# Expan.net
KiCad netlist of a schematic drawn in Altium Designer
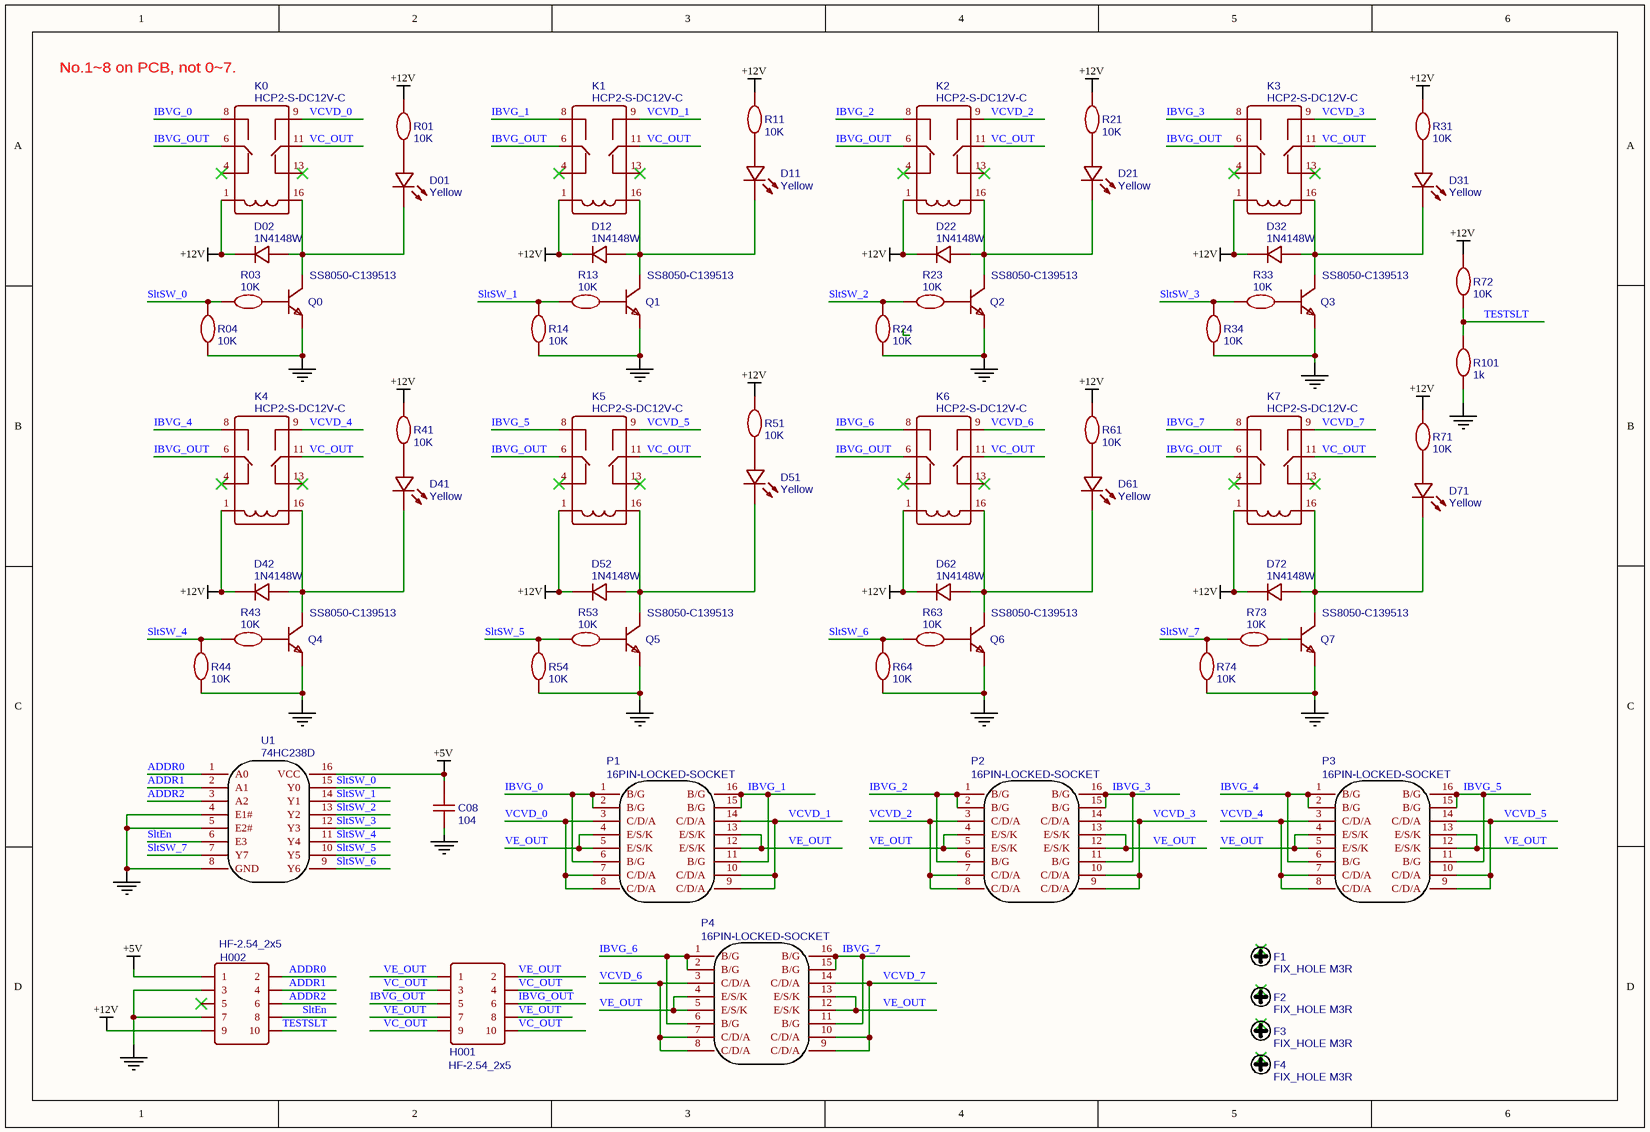
[diagram p0: Expan.schdoc]

(export (version "E")
  (design (tool "Eeschema 10.0.6"))
  (components
    (comp (ref "C08")
      (value "104")
      (footprint "C0805")
      (libsource (lib "altium-import") (part "root_0_104_"))
    )
    (comp (ref "D01")
      (value "Yellow")
      (footprint "LED-TH_BD4.0-P2.54-FD")
      (fields
        (field (name "BOM_SUPPLIER PART") "C396687")
        (field (name "BOM_MANUFACTURER PART") "DY-204URD/SN-A3(EL)")
        (field (name "CONTRIBUTOR") "LCSC")
      )
      (libsource (lib "altium-import") (part "root_3_Yellow_"))
    )
    (comp (ref "D02")
      (value "1N4148W")
      (footprint "SOD-123_L2.8-W1.8-LS3.7-FD")
      (fields (field (name "BOM_SUPPLIER PART") "C81598"))
      (libsource (lib "altium-import") (part "root_2_1N4148W_"))
    )
    (comp (ref "D11")
      (value "Yellow")
      (footprint "LED-TH_BD4.0-P2.54-FD")
      (fields
        (field (name "BOM_SUPPLIER PART") "C396687")
        (field (name "BOM_MANUFACTURER PART") "DY-204URD/SN-A3(EL)")
        (field (name "CONTRIBUTOR") "LCSC")
      )
      (libsource (lib "altium-import") (part "root_3_Yellow_"))
    )
    (comp (ref "D12")
      (value "1N4148W")
      (footprint "SOD-123_L2.8-W1.8-LS3.7-FD")
      (fields (field (name "BOM_SUPPLIER PART") "C81598"))
      (libsource (lib "altium-import") (part "root_2_1N4148W_"))
    )
    (comp (ref "D21")
      (value "Yellow")
      (footprint "LED-TH_BD4.0-P2.54-FD")
      (fields
        (field (name "BOM_SUPPLIER PART") "C396687")
        (field (name "BOM_MANUFACTURER PART") "DY-204URD/SN-A3(EL)")
        (field (name "CONTRIBUTOR") "LCSC")
      )
      (libsource (lib "altium-import") (part "root_3_Yellow_"))
    )
    (comp (ref "D22")
      (value "1N4148W")
      (footprint "SOD-123_L2.8-W1.8-LS3.7-FD")
      (fields (field (name "BOM_SUPPLIER PART") "C81598"))
      (libsource (lib "altium-import") (part "root_2_1N4148W_"))
    )
    (comp (ref "D31")
      (value "Yellow")
      (footprint "LED-TH_BD4.0-P2.54-FD")
      (fields
        (field (name "BOM_SUPPLIER PART") "C396687")
        (field (name "BOM_MANUFACTURER PART") "DY-204URD/SN-A3(EL)")
        (field (name "CONTRIBUTOR") "LCSC")
      )
      (libsource (lib "altium-import") (part "root_3_Yellow_"))
    )
    (comp (ref "D32")
      (value "1N4148W")
      (footprint "SOD-123_L2.8-W1.8-LS3.7-FD")
      (fields (field (name "BOM_SUPPLIER PART") "C81598"))
      (libsource (lib "altium-import") (part "root_2_1N4148W_"))
    )
    (comp (ref "D41")
      (value "Yellow")
      (footprint "LED-TH_BD4.0-P2.54-FD")
      (fields
        (field (name "BOM_SUPPLIER PART") "C396687")
        (field (name "BOM_MANUFACTURER PART") "DY-204URD/SN-A3(EL)")
        (field (name "CONTRIBUTOR") "LCSC")
      )
      (libsource (lib "altium-import") (part "root_3_Yellow_"))
    )
    (comp (ref "D42")
      (value "1N4148W")
      (footprint "SOD-123_L2.8-W1.8-LS3.7-FD")
      (fields (field (name "BOM_SUPPLIER PART") "C81598"))
      (libsource (lib "altium-import") (part "root_2_1N4148W_"))
    )
    (comp (ref "D51")
      (value "Yellow")
      (footprint "LED-TH_BD4.0-P2.54-FD")
      (fields
        (field (name "BOM_SUPPLIER PART") "C396687")
        (field (name "BOM_MANUFACTURER PART") "DY-204URD/SN-A3(EL)")
        (field (name "CONTRIBUTOR") "LCSC")
      )
      (libsource (lib "altium-import") (part "root_3_Yellow_"))
    )
    (comp (ref "D52")
      (value "1N4148W")
      (footprint "SOD-123_L2.8-W1.8-LS3.7-FD")
      (fields (field (name "BOM_SUPPLIER PART") "C81598"))
      (libsource (lib "altium-import") (part "root_2_1N4148W_"))
    )
    (comp (ref "D61")
      (value "Yellow")
      (footprint "LED-TH_BD4.0-P2.54-FD")
      (fields
        (field (name "BOM_SUPPLIER PART") "C396687")
        (field (name "BOM_MANUFACTURER PART") "DY-204URD/SN-A3(EL)")
        (field (name "CONTRIBUTOR") "LCSC")
      )
      (libsource (lib "altium-import") (part "root_3_Yellow_"))
    )
    (comp (ref "D62")
      (value "1N4148W")
      (footprint "SOD-123_L2.8-W1.8-LS3.7-FD")
      (fields (field (name "BOM_SUPPLIER PART") "C81598"))
      (libsource (lib "altium-import") (part "root_2_1N4148W_"))
    )
    (comp (ref "D71")
      (value "Yellow")
      (footprint "LED-TH_BD4.0-P2.54-FD")
      (fields
        (field (name "BOM_SUPPLIER PART") "C396687")
        (field (name "BOM_MANUFACTURER PART") "DY-204URD/SN-A3(EL)")
        (field (name "CONTRIBUTOR") "LCSC")
      )
      (libsource (lib "altium-import") (part "root_3_Yellow_"))
    )
    (comp (ref "D72")
      (value "1N4148W")
      (footprint "SOD-123_L2.8-W1.8-LS3.7-FD")
      (fields (field (name "BOM_SUPPLIER PART") "C81598"))
      (libsource (lib "altium-import") (part "root_2_1N4148W_"))
    )
    (comp (ref "F1")
      (value "FIX_HOLE M3R")
      (footprint "FIXHOLE_M3R")
      (fields (field (name "CONTRIBUTOR") "JM共享库"))
      (libsource (lib "altium-import") (part "root_0_FIX_HOLE M3R_"))
    )
    (comp (ref "F2")
      (value "FIX_HOLE M3R")
      (footprint "FIXHOLE_M3R")
      (fields (field (name "CONTRIBUTOR") "JM共享库"))
      (libsource (lib "altium-import") (part "root_0_FIX_HOLE M3R_"))
    )
    (comp (ref "F3")
      (value "FIX_HOLE M3R")
      (footprint "FIXHOLE_M3R")
      (fields (field (name "CONTRIBUTOR") "JM共享库"))
      (libsource (lib "altium-import") (part "root_0_FIX_HOLE M3R_"))
    )
    (comp (ref "F4")
      (value "FIX_HOLE M3R")
      (footprint "FIXHOLE_M3R")
      (fields (field (name "CONTRIBUTOR") "JM共享库"))
      (libsource (lib "altium-import") (part "root_0_FIX_HOLE M3R_"))
    )
    (comp (ref "H001")
      (value "HF-2.54_2x5")
      (footprint "HDR-TH_10P-P2.54-V-R2-C5-S2.54")
      (fields
        (field (name "BOM_MANUFACTURER PART") "220S-2*5P H=8.5MM Ytype Gold-plated")
        (field (name "BOM_SUPPLIER PART") "C124423")
      )
      (libsource (lib "altium-import") (part "root_0_HF-2.54_2x5_"))
    )
    (comp (ref "H002")
      (value "HF-2.54_2x5")
      (footprint "HDR-TH_10P-P2.54-V-R2-C5-S2.54")
      (fields
        (field (name "BOM_MANUFACTURER PART") "220S-2*5P H=8.5MM Ytype Gold-plated")
        (field (name "BOM_SUPPLIER PART") "C124423")
      )
      (libsource (lib "altium-import") (part "root_0_HF-2.54_2x5_"))
    )
    (comp (ref "K0")
      (value "HCP2-S-DC12V-C")
      (footprint "RELAY-HCP2-S-C")
      (fields (field (name "BOM_SUPPLIER PART") "C125698") (field (name "CONTRIBUTOR") "LCSC"))
      (libsource (lib "altium-import") (part "root_1_HCP2-S-DC12V-C_"))
    )
    (comp (ref "K1")
      (value "HCP2-S-DC12V-C")
      (footprint "RELAY-HCP2-S-C")
      (fields (field (name "BOM_SUPPLIER PART") "C125698") (field (name "CONTRIBUTOR") "LCSC"))
      (libsource (lib "altium-import") (part "root_1_HCP2-S-DC12V-C_"))
    )
    (comp (ref "K2")
      (value "HCP2-S-DC12V-C")
      (footprint "RELAY-HCP2-S-C")
      (fields (field (name "BOM_SUPPLIER PART") "C125698") (field (name "CONTRIBUTOR") "LCSC"))
      (libsource (lib "altium-import") (part "root_1_HCP2-S-DC12V-C_"))
    )
    (comp (ref "K3")
      (value "HCP2-S-DC12V-C")
      (footprint "RELAY-HCP2-S-C")
      (fields (field (name "BOM_SUPPLIER PART") "C125698") (field (name "CONTRIBUTOR") "LCSC"))
      (libsource (lib "altium-import") (part "root_1_HCP2-S-DC12V-C_"))
    )
    (comp (ref "K4")
      (value "HCP2-S-DC12V-C")
      (footprint "RELAY-HCP2-S-C")
      (fields (field (name "BOM_SUPPLIER PART") "C125698") (field (name "CONTRIBUTOR") "LCSC"))
      (libsource (lib "altium-import") (part "root_1_HCP2-S-DC12V-C_"))
    )
    (comp (ref "K5")
      (value "HCP2-S-DC12V-C")
      (footprint "RELAY-HCP2-S-C")
      (fields (field (name "BOM_SUPPLIER PART") "C125698") (field (name "CONTRIBUTOR") "LCSC"))
      (libsource (lib "altium-import") (part "root_1_HCP2-S-DC12V-C_"))
    )
    (comp (ref "K6")
      (value "HCP2-S-DC12V-C")
      (footprint "RELAY-HCP2-S-C")
      (fields (field (name "BOM_SUPPLIER PART") "C125698") (field (name "CONTRIBUTOR") "LCSC"))
      (libsource (lib "altium-import") (part "root_1_HCP2-S-DC12V-C_"))
    )
    (comp (ref "K7")
      (value "HCP2-S-DC12V-C")
      (footprint "RELAY-HCP2-S-C")
      (fields (field (name "BOM_SUPPLIER PART") "C125698") (field (name "CONTRIBUTOR") "LCSC"))
      (libsource (lib "altium-import") (part "root_1_HCP2-S-DC12V-C_"))
    )
    (comp (ref "P1")
      (value "16PIN-LOCKED-SOCKET")
      (footprint "16PIN-LOCKED-SOCKET")
      (fields (field (name "CONTRIBUTOR") "XTX_AE"))
      (libsource (lib "altium-import") (part "root_0_16PIN-LOCKED-SOCKET_"))
    )
    (comp (ref "P2")
      (value "16PIN-LOCKED-SOCKET")
      (footprint "16PIN-LOCKED-SOCKET")
      (fields (field (name "CONTRIBUTOR") "XTX_AE"))
      (libsource (lib "altium-import") (part "root_0_16PIN-LOCKED-SOCKET_"))
    )
    (comp (ref "P3")
      (value "16PIN-LOCKED-SOCKET")
      (footprint "16PIN-LOCKED-SOCKET")
      (fields (field (name "CONTRIBUTOR") "XTX_AE"))
      (libsource (lib "altium-import") (part "root_0_16PIN-LOCKED-SOCKET_"))
    )
    (comp (ref "P4")
      (value "16PIN-LOCKED-SOCKET")
      (footprint "16PIN-LOCKED-SOCKET")
      (fields (field (name "CONTRIBUTOR") "XTX_AE"))
      (libsource (lib "altium-import") (part "root_0_16PIN-LOCKED-SOCKET_"))
    )
    (comp (ref "Q0")
      (value "SS8050-C139513")
      (footprint "SOT-23-3_L2.9-W1.3-P1.90-LS2.4-BR")
      (fields
        (field (name "BOM_SUPPLIER PART") "C402304")
        (field (name "BOM_MANUFACTURER PART") "SS8050")
        (field (name "CONTRIBUTOR") "LCSC")
      )
      (libsource (lib "altium-import") (part "root_0_SS8050-C139513_"))
    )
    (comp (ref "Q1")
      (value "SS8050-C139513")
      (footprint "SOT-23-3_L2.9-W1.3-P1.90-LS2.4-BR")
      (fields
        (field (name "BOM_SUPPLIER PART") "C402304")
        (field (name "BOM_MANUFACTURER PART") "SS8050")
        (field (name "CONTRIBUTOR") "LCSC")
      )
      (libsource (lib "altium-import") (part "root_0_SS8050-C139513_"))
    )
    (comp (ref "Q2")
      (value "SS8050-C139513")
      (footprint "SOT-23-3_L2.9-W1.3-P1.90-LS2.4-BR")
      (fields
        (field (name "BOM_SUPPLIER PART") "C402304")
        (field (name "BOM_MANUFACTURER PART") "SS8050")
        (field (name "CONTRIBUTOR") "LCSC")
      )
      (libsource (lib "altium-import") (part "root_0_SS8050-C139513_"))
    )
    (comp (ref "Q3")
      (value "SS8050-C139513")
      (footprint "SOT-23-3_L2.9-W1.3-P1.90-LS2.4-BR")
      (fields
        (field (name "BOM_SUPPLIER PART") "C402304")
        (field (name "BOM_MANUFACTURER PART") "SS8050")
        (field (name "CONTRIBUTOR") "LCSC")
      )
      (libsource (lib "altium-import") (part "root_0_SS8050-C139513_"))
    )
    (comp (ref "Q4")
      (value "SS8050-C139513")
      (footprint "SOT-23-3_L2.9-W1.3-P1.90-LS2.4-BR")
      (fields
        (field (name "BOM_SUPPLIER PART") "C402304")
        (field (name "BOM_MANUFACTURER PART") "SS8050")
        (field (name "CONTRIBUTOR") "LCSC")
      )
      (libsource (lib "altium-import") (part "root_0_SS8050-C139513_"))
    )
    (comp (ref "Q5")
      (value "SS8050-C139513")
      (footprint "SOT-23-3_L2.9-W1.3-P1.90-LS2.4-BR")
      (fields
        (field (name "BOM_SUPPLIER PART") "C402304")
        (field (name "BOM_MANUFACTURER PART") "SS8050")
        (field (name "CONTRIBUTOR") "LCSC")
      )
      (libsource (lib "altium-import") (part "root_0_SS8050-C139513_"))
    )
    (comp (ref "Q6")
      (value "SS8050-C139513")
      (footprint "SOT-23-3_L2.9-W1.3-P1.90-LS2.4-BR")
      (fields
        (field (name "BOM_SUPPLIER PART") "C402304")
        (field (name "BOM_MANUFACTURER PART") "SS8050")
        (field (name "CONTRIBUTOR") "LCSC")
      )
      (libsource (lib "altium-import") (part "root_0_SS8050-C139513_"))
    )
    (comp (ref "Q7")
      (value "SS8050-C139513")
      (footprint "SOT-23-3_L2.9-W1.3-P1.90-LS2.4-BR")
      (fields
        (field (name "BOM_SUPPLIER PART") "C402304")
        (field (name "BOM_MANUFACTURER PART") "SS8050")
        (field (name "CONTRIBUTOR") "LCSC")
      )
      (libsource (lib "altium-import") (part "root_0_SS8050-C139513_"))
    )
    (comp (ref "R01")
      (value "10K")
      (footprint "R0805")
      (libsource (lib "altium-import") (part "root_3_10K_"))
    )
    (comp (ref "R03")
      (value "10K")
      (footprint "R0805")
      (libsource (lib "altium-import") (part "root_2_10K_"))
    )
    (comp (ref "R04")
      (value "10K")
      (footprint "R0805")
      (libsource (lib "altium-import") (part "root_3_10K_"))
    )
    (comp (ref "R11")
      (value "10K")
      (footprint "R0805")
      (libsource (lib "altium-import") (part "root_3_10K_"))
    )
    (comp (ref "R13")
      (value "10K")
      (footprint "R0805")
      (libsource (lib "altium-import") (part "root_2_10K_"))
    )
    (comp (ref "R14")
      (value "10K")
      (footprint "R0805")
      (libsource (lib "altium-import") (part "root_3_10K_"))
    )
    (comp (ref "R21")
      (value "10K")
      (footprint "R0805")
      (libsource (lib "altium-import") (part "root_3_10K_"))
    )
    (comp (ref "R23")
      (value "10K")
      (footprint "R0805")
      (libsource (lib "altium-import") (part "root_2_10K_"))
    )
    (comp (ref "R24")
      (value "10K")
      (footprint "R0805")
      (libsource (lib "altium-import") (part "root_3_10K_"))
    )
    (comp (ref "R31")
      (value "10K")
      (footprint "R0805")
      (libsource (lib "altium-import") (part "root_3_10K_"))
    )
    (comp (ref "R33")
      (value "10K")
      (footprint "R0805")
      (libsource (lib "altium-import") (part "root_2_10K_"))
    )
    (comp (ref "R34")
      (value "10K")
      (footprint "R0805")
      (libsource (lib "altium-import") (part "root_3_10K_"))
    )
    (comp (ref "R41")
      (value "10K")
      (footprint "R0805")
      (libsource (lib "altium-import") (part "root_3_10K_"))
    )
    (comp (ref "R43")
      (value "10K")
      (footprint "R0805")
      (libsource (lib "altium-import") (part "root_2_10K_"))
    )
    (comp (ref "R44")
      (value "10K")
      (footprint "R0805")
      (libsource (lib "altium-import") (part "root_3_10K_"))
    )
    (comp (ref "R51")
      (value "10K")
      (footprint "R0805")
      (libsource (lib "altium-import") (part "root_3_10K_"))
    )
    (comp (ref "R53")
      (value "10K")
      (footprint "R0805")
      (libsource (lib "altium-import") (part "root_2_10K_"))
    )
    (comp (ref "R54")
      (value "10K")
      (footprint "R0805")
      (libsource (lib "altium-import") (part "root_3_10K_"))
    )
    (comp (ref "R61")
      (value "10K")
      (footprint "R0805")
      (libsource (lib "altium-import") (part "root_3_10K_"))
    )
    (comp (ref "R63")
      (value "10K")
      (footprint "R0805")
      (libsource (lib "altium-import") (part "root_2_10K_"))
    )
    (comp (ref "R64")
      (value "10K")
      (footprint "R0805")
      (libsource (lib "altium-import") (part "root_3_10K_"))
    )
    (comp (ref "R71")
      (value "10K")
      (footprint "R0805")
      (libsource (lib "altium-import") (part "root_3_10K_"))
    )
    (comp (ref "R72")
      (value "10K")
      (footprint "R0805")
      (libsource (lib "altium-import") (part "root_3_10K_"))
    )
    (comp (ref "R73")
      (value "10K")
      (footprint "R0805")
      (libsource (lib "altium-import") (part "root_2_10K_"))
    )
    (comp (ref "R74")
      (value "10K")
      (footprint "R0805")
      (libsource (lib "altium-import") (part "root_3_10K_"))
    )
    (comp (ref "R101") (value "1k") (footprint "R0805") (libsource (lib "altium-import") (part "root_3_1k_")))
    (comp (ref "U1")
      (value "74HC238D")
      (footprint "SOIC-16_L9.9-W3.9-P1.27-LS6.0-BL")
      (fields (field (name "BOM_SUPPLIER PART") "C5620"))
      (libsource (lib "altium-import") (part "root_0_74HC238D_"))
    )
  )
  (nets
    (net (code "1") (name "+5V") (class "Default")
      (node (ref "C08") (pin "2") (pinfunction "2_2") (pintype "passive"))
      (node (ref "H002") (pin "1") (pinfunction "1_1") (pintype "passive"))
      (node (ref "U1") (pin "16") (pinfunction "VCC_16") (pintype "passive"))
    )
    (net (code "2") (name "+12V") (class "Default")
      (node (ref "D02") (pin "2") (pinfunction "K_2") (pintype "passive"))
      (node (ref "D12") (pin "2") (pinfunction "K_2") (pintype "passive"))
      (node (ref "D22") (pin "2") (pinfunction "K_2") (pintype "passive"))
      (node (ref "D32") (pin "2") (pinfunction "K_2") (pintype "passive"))
      (node (ref "D42") (pin "2") (pinfunction "K_2") (pintype "passive"))
      (node (ref "D52") (pin "2") (pinfunction "K_2") (pintype "passive"))
      (node (ref "D62") (pin "2") (pinfunction "K_2") (pintype "passive"))
      (node (ref "D72") (pin "2") (pinfunction "K_2") (pintype "passive"))
      (node (ref "H002") (pin "9") (pinfunction "9_9") (pintype "passive"))
      (node (ref "K0") (pin "1") (pinfunction "1_1") (pintype "passive"))
      (node (ref "K1") (pin "1") (pinfunction "1_1") (pintype "passive"))
      (node (ref "K2") (pin "1") (pinfunction "1_1") (pintype "passive"))
      (node (ref "K3") (pin "1") (pinfunction "1_1") (pintype "passive"))
      (node (ref "K4") (pin "1") (pinfunction "1_1") (pintype "passive"))
      (node (ref "K5") (pin "1") (pinfunction "1_1") (pintype "passive"))
      (node (ref "K6") (pin "1") (pinfunction "1_1") (pintype "passive"))
      (node (ref "K7") (pin "1") (pinfunction "1_1") (pintype "passive"))
      (node (ref "R01") (pin "1") (pinfunction "1_1") (pintype "passive"))
      (node (ref "R11") (pin "1") (pinfunction "1_1") (pintype "passive"))
      (node (ref "R21") (pin "1") (pinfunction "1_1") (pintype "passive"))
      (node (ref "R31") (pin "1") (pinfunction "1_1") (pintype "passive"))
      (node (ref "R41") (pin "1") (pinfunction "1_1") (pintype "passive"))
      (node (ref "R51") (pin "1") (pinfunction "1_1") (pintype "passive"))
      (node (ref "R61") (pin "1") (pinfunction "1_1") (pintype "passive"))
      (node (ref "R71") (pin "1") (pinfunction "1_1") (pintype "passive"))
      (node (ref "R72") (pin "1") (pinfunction "1_1") (pintype "passive"))
    )
    (net (code "3") (name "/ADDR0") (class "Default")
      (node (ref "H002") (pin "2") (pinfunction "2_2") (pintype "passive"))
      (node (ref "U1") (pin "1") (pinfunction "A0_1") (pintype "passive"))
    )
    (net (code "4") (name "/ADDR1") (class "Default")
      (node (ref "H002") (pin "4") (pinfunction "4_4") (pintype "passive"))
      (node (ref "U1") (pin "2") (pinfunction "A1_2") (pintype "passive"))
    )
    (net (code "5") (name "/ADDR2") (class "Default")
      (node (ref "H002") (pin "6") (pinfunction "6_6") (pintype "passive"))
      (node (ref "U1") (pin "3") (pinfunction "A2_3") (pintype "passive"))
    )
    (net (code "6") (name "/IBVG_0") (class "Default")
      (node (ref "K0") (pin "8") (pinfunction "8_8") (pintype "passive"))
      (node (ref "P1") (pin "1") (pinfunction "B/G_1") (pintype "passive"))
      (node (ref "P1") (pin "2") (pinfunction "B/G_2") (pintype "passive"))
      (node (ref "P1") (pin "6") (pinfunction "B/G_6") (pintype "passive"))
    )
    (net (code "7") (name "/IBVG_1") (class "Default")
      (node (ref "K1") (pin "8") (pinfunction "8_8") (pintype "passive"))
      (node (ref "P1") (pin "11") (pinfunction "B/G_11") (pintype "passive"))
      (node (ref "P1") (pin "15") (pinfunction "B/G_15") (pintype "passive"))
      (node (ref "P1") (pin "16") (pinfunction "B/G_16") (pintype "passive"))
    )
    (net (code "8") (name "/IBVG_2") (class "Default")
      (node (ref "K2") (pin "8") (pinfunction "8_8") (pintype "passive"))
      (node (ref "P2") (pin "1") (pinfunction "B/G_1") (pintype "passive"))
      (node (ref "P2") (pin "2") (pinfunction "B/G_2") (pintype "passive"))
      (node (ref "P2") (pin "6") (pinfunction "B/G_6") (pintype "passive"))
    )
    (net (code "9") (name "/IBVG_3") (class "Default")
      (node (ref "K3") (pin "8") (pinfunction "8_8") (pintype "passive"))
      (node (ref "P2") (pin "11") (pinfunction "B/G_11") (pintype "passive"))
      (node (ref "P2") (pin "15") (pinfunction "B/G_15") (pintype "passive"))
      (node (ref "P2") (pin "16") (pinfunction "B/G_16") (pintype "passive"))
    )
    (net (code "10") (name "/IBVG_4") (class "Default")
      (node (ref "K4") (pin "8") (pinfunction "8_8") (pintype "passive"))
      (node (ref "P3") (pin "1") (pinfunction "B/G_1") (pintype "passive"))
      (node (ref "P3") (pin "2") (pinfunction "B/G_2") (pintype "passive"))
      (node (ref "P3") (pin "6") (pinfunction "B/G_6") (pintype "passive"))
    )
    (net (code "11") (name "/IBVG_5") (class "Default")
      (node (ref "K5") (pin "8") (pinfunction "8_8") (pintype "passive"))
      (node (ref "P3") (pin "11") (pinfunction "B/G_11") (pintype "passive"))
      (node (ref "P3") (pin "15") (pinfunction "B/G_15") (pintype "passive"))
      (node (ref "P3") (pin "16") (pinfunction "B/G_16") (pintype "passive"))
    )
    (net (code "12") (name "/IBVG_6") (class "Default")
      (node (ref "K6") (pin "8") (pinfunction "8_8") (pintype "passive"))
      (node (ref "P4") (pin "1") (pinfunction "B/G_1") (pintype "passive"))
      (node (ref "P4") (pin "2") (pinfunction "B/G_2") (pintype "passive"))
      (node (ref "P4") (pin "6") (pinfunction "B/G_6") (pintype "passive"))
    )
    (net (code "13") (name "/IBVG_7") (class "Default")
      (node (ref "K7") (pin "8") (pinfunction "8_8") (pintype "passive"))
      (node (ref "P4") (pin "11") (pinfunction "B/G_11") (pintype "passive"))
      (node (ref "P4") (pin "15") (pinfunction "B/G_15") (pintype "passive"))
      (node (ref "P4") (pin "16") (pinfunction "B/G_16") (pintype "passive"))
    )
    (net (code "14") (name "/IBVG_OUT") (class "Default")
      (node (ref "H001") (pin "5") (pinfunction "5_5") (pintype "passive"))
      (node (ref "H001") (pin "6") (pinfunction "6_6") (pintype "passive"))
      (node (ref "K0") (pin "6") (pinfunction "6_6") (pintype "passive"))
      (node (ref "K1") (pin "6") (pinfunction "6_6") (pintype "passive"))
      (node (ref "K2") (pin "6") (pinfunction "6_6") (pintype "passive"))
      (node (ref "K3") (pin "6") (pinfunction "6_6") (pintype "passive"))
      (node (ref "K4") (pin "6") (pinfunction "6_6") (pintype "passive"))
      (node (ref "K5") (pin "6") (pinfunction "6_6") (pintype "passive"))
      (node (ref "K6") (pin "6") (pinfunction "6_6") (pintype "passive"))
      (node (ref "K7") (pin "6") (pinfunction "6_6") (pintype "passive"))
    )
    (net (code "15") (name "/SltEn") (class "Default")
      (node (ref "H002") (pin "8") (pinfunction "8_8") (pintype "passive"))
      (node (ref "U1") (pin "6") (pinfunction "E3_6") (pintype "passive"))
    )
    (net (code "16") (name "/SltSW_0") (class "Default")
      (node (ref "R03") (pin "2") (pinfunction "2_2") (pintype "passive"))
      (node (ref "R04") (pin "1") (pinfunction "1_1") (pintype "passive"))
      (node (ref "U1") (pin "15") (pinfunction "Y0_15") (pintype "passive"))
    )
    (net (code "17") (name "/SltSW_1") (class "Default")
      (node (ref "R13") (pin "2") (pinfunction "2_2") (pintype "passive"))
      (node (ref "R14") (pin "1") (pinfunction "1_1") (pintype "passive"))
      (node (ref "U1") (pin "14") (pinfunction "Y1_14") (pintype "passive"))
    )
    (net (code "18") (name "/SltSW_2") (class "Default")
      (node (ref "R23") (pin "2") (pinfunction "2_2") (pintype "passive"))
      (node (ref "R24") (pin "1") (pinfunction "1_1") (pintype "passive"))
      (node (ref "U1") (pin "13") (pinfunction "Y2_13") (pintype "passive"))
    )
    (net (code "19") (name "/SltSW_3") (class "Default")
      (node (ref "R33") (pin "2") (pinfunction "2_2") (pintype "passive"))
      (node (ref "R34") (pin "1") (pinfunction "1_1") (pintype "passive"))
      (node (ref "U1") (pin "12") (pinfunction "Y3_12") (pintype "passive"))
    )
    (net (code "20") (name "/SltSW_4") (class "Default")
      (node (ref "R43") (pin "2") (pinfunction "2_2") (pintype "passive"))
      (node (ref "R44") (pin "1") (pinfunction "1_1") (pintype "passive"))
      (node (ref "U1") (pin "11") (pinfunction "Y4_11") (pintype "passive"))
    )
    (net (code "21") (name "/SltSW_5") (class "Default")
      (node (ref "R53") (pin "2") (pinfunction "2_2") (pintype "passive"))
      (node (ref "R54") (pin "1") (pinfunction "1_1") (pintype "passive"))
      (node (ref "U1") (pin "10") (pinfunction "Y5_10") (pintype "passive"))
    )
    (net (code "22") (name "/SltSW_6") (class "Default")
      (node (ref "R63") (pin "2") (pinfunction "2_2") (pintype "passive"))
      (node (ref "R64") (pin "1") (pinfunction "1_1") (pintype "passive"))
      (node (ref "U1") (pin "9") (pinfunction "Y6_9") (pintype "passive"))
    )
    (net (code "23") (name "/SltSW_7") (class "Default")
      (node (ref "R73") (pin "2") (pinfunction "2_2") (pintype "passive"))
      (node (ref "R74") (pin "1") (pinfunction "1_1") (pintype "passive"))
      (node (ref "U1") (pin "7") (pinfunction "Y7_7") (pintype "passive"))
    )
    (net (code "24") (name "/TESTSLT") (class "Default")
      (node (ref "H002") (pin "10") (pinfunction "10_10") (pintype "passive"))
      (node (ref "R101") (pin "1") (pinfunction "1_1") (pintype "passive"))
      (node (ref "R72") (pin "2") (pinfunction "2_2") (pintype "passive"))
    )
    (net (code "25") (name "/VCVD_0") (class "Default")
      (node (ref "K0") (pin "9") (pinfunction "9_9") (pintype "passive"))
      (node (ref "P1") (pin "3") (pinfunction "C/D/A_3") (pintype "passive"))
      (node (ref "P1") (pin "7") (pinfunction "C/D/A_7") (pintype "passive"))
      (node (ref "P1") (pin "8") (pinfunction "C/D/A_8") (pintype "passive"))
    )
    (net (code "26") (name "/VCVD_1") (class "Default")
      (node (ref "K1") (pin "9") (pinfunction "9_9") (pintype "passive"))
      (node (ref "P1") (pin "10") (pinfunction "C/D/A_10") (pintype "passive"))
      (node (ref "P1") (pin "14") (pinfunction "C/D/A_14") (pintype "passive"))
      (node (ref "P1") (pin "9") (pinfunction "C/D/A_9") (pintype "passive"))
    )
    (net (code "27") (name "/VCVD_2") (class "Default")
      (node (ref "K2") (pin "9") (pinfunction "9_9") (pintype "passive"))
      (node (ref "P2") (pin "3") (pinfunction "C/D/A_3") (pintype "passive"))
      (node (ref "P2") (pin "7") (pinfunction "C/D/A_7") (pintype "passive"))
      (node (ref "P2") (pin "8") (pinfunction "C/D/A_8") (pintype "passive"))
    )
    (net (code "28") (name "/VCVD_3") (class "Default")
      (node (ref "K3") (pin "9") (pinfunction "9_9") (pintype "passive"))
      (node (ref "P2") (pin "10") (pinfunction "C/D/A_10") (pintype "passive"))
      (node (ref "P2") (pin "14") (pinfunction "C/D/A_14") (pintype "passive"))
      (node (ref "P2") (pin "9") (pinfunction "C/D/A_9") (pintype "passive"))
    )
    (net (code "29") (name "/VCVD_4") (class "Default")
      (node (ref "K4") (pin "9") (pinfunction "9_9") (pintype "passive"))
      (node (ref "P3") (pin "3") (pinfunction "C/D/A_3") (pintype "passive"))
      (node (ref "P3") (pin "7") (pinfunction "C/D/A_7") (pintype "passive"))
      (node (ref "P3") (pin "8") (pinfunction "C/D/A_8") (pintype "passive"))
    )
    (net (code "30") (name "/VCVD_5") (class "Default")
      (node (ref "K5") (pin "9") (pinfunction "9_9") (pintype "passive"))
      (node (ref "P3") (pin "10") (pinfunction "C/D/A_10") (pintype "passive"))
      (node (ref "P3") (pin "14") (pinfunction "C/D/A_14") (pintype "passive"))
      (node (ref "P3") (pin "9") (pinfunction "C/D/A_9") (pintype "passive"))
    )
    (net (code "31") (name "/VCVD_6") (class "Default")
      (node (ref "K6") (pin "9") (pinfunction "9_9") (pintype "passive"))
      (node (ref "P4") (pin "3") (pinfunction "C/D/A_3") (pintype "passive"))
      (node (ref "P4") (pin "7") (pinfunction "C/D/A_7") (pintype "passive"))
      (node (ref "P4") (pin "8") (pinfunction "C/D/A_8") (pintype "passive"))
    )
    (net (code "32") (name "/VCVD_7") (class "Default")
      (node (ref "K7") (pin "9") (pinfunction "9_9") (pintype "passive"))
      (node (ref "P4") (pin "10") (pinfunction "C/D/A_10") (pintype "passive"))
      (node (ref "P4") (pin "14") (pinfunction "C/D/A_14") (pintype "passive"))
      (node (ref "P4") (pin "9") (pinfunction "C/D/A_9") (pintype "passive"))
    )
    (net (code "33") (name "/VC_OUT") (class "Default")
      (node (ref "H001") (pin "10") (pinfunction "10_10") (pintype "passive"))
      (node (ref "H001") (pin "3") (pinfunction "3_3") (pintype "passive"))
      (node (ref "H001") (pin "4") (pinfunction "4_4") (pintype "passive"))
      (node (ref "H001") (pin "9") (pinfunction "9_9") (pintype "passive"))
      (node (ref "K0") (pin "11") (pinfunction "11_11") (pintype "passive"))
      (node (ref "K1") (pin "11") (pinfunction "11_11") (pintype "passive"))
      (node (ref "K2") (pin "11") (pinfunction "11_11") (pintype "passive"))
      (node (ref "K3") (pin "11") (pinfunction "11_11") (pintype "passive"))
      (node (ref "K4") (pin "11") (pinfunction "11_11") (pintype "passive"))
      (node (ref "K5") (pin "11") (pinfunction "11_11") (pintype "passive"))
      (node (ref "K6") (pin "11") (pinfunction "11_11") (pintype "passive"))
      (node (ref "K7") (pin "11") (pinfunction "11_11") (pintype "passive"))
    )
    (net (code "34") (name "/VE_OUT") (class "Default")
      (node (ref "H001") (pin "1") (pinfunction "1_1") (pintype "passive"))
      (node (ref "H001") (pin "2") (pinfunction "2_2") (pintype "passive"))
      (node (ref "H001") (pin "7") (pinfunction "7_7") (pintype "passive"))
      (node (ref "H001") (pin "8") (pinfunction "8_8") (pintype "passive"))
      (node (ref "P1") (pin "12") (pinfunction "E/S/K_12") (pintype "passive"))
      (node (ref "P1") (pin "13") (pinfunction "E/S/K_13") (pintype "passive"))
      (node (ref "P1") (pin "4") (pinfunction "E/S/K_4") (pintype "passive"))
      (node (ref "P1") (pin "5") (pinfunction "E/S/K_5") (pintype "passive"))
      (node (ref "P2") (pin "12") (pinfunction "E/S/K_12") (pintype "passive"))
      (node (ref "P2") (pin "13") (pinfunction "E/S/K_13") (pintype "passive"))
      (node (ref "P2") (pin "4") (pinfunction "E/S/K_4") (pintype "passive"))
      (node (ref "P2") (pin "5") (pinfunction "E/S/K_5") (pintype "passive"))
      (node (ref "P3") (pin "12") (pinfunction "E/S/K_12") (pintype "passive"))
      (node (ref "P3") (pin "13") (pinfunction "E/S/K_13") (pintype "passive"))
      (node (ref "P3") (pin "4") (pinfunction "E/S/K_4") (pintype "passive"))
      (node (ref "P3") (pin "5") (pinfunction "E/S/K_5") (pintype "passive"))
      (node (ref "P4") (pin "12") (pinfunction "E/S/K_12") (pintype "passive"))
      (node (ref "P4") (pin "13") (pinfunction "E/S/K_13") (pintype "passive"))
      (node (ref "P4") (pin "4") (pinfunction "E/S/K_4") (pintype "passive"))
      (node (ref "P4") (pin "5") (pinfunction "E/S/K_5") (pintype "passive"))
    )
    (net (code "35") (name "GND") (class "Default")
      (node (ref "C08") (pin "1") (pinfunction "1_1") (pintype "passive"))
      (node (ref "H002") (pin "3") (pinfunction "3_3") (pintype "passive"))
      (node (ref "H002") (pin "7") (pinfunction "7_7") (pintype "passive"))
      (node (ref "Q0") (pin "2") (pinfunction "E_2") (pintype "passive"))
      (node (ref "Q1") (pin "2") (pinfunction "E_2") (pintype "passive"))
      (node (ref "Q2") (pin "2") (pinfunction "E_2") (pintype "passive"))
      (node (ref "Q3") (pin "2") (pinfunction "E_2") (pintype "passive"))
      (node (ref "Q4") (pin "2") (pinfunction "E_2") (pintype "passive"))
      (node (ref "Q5") (pin "2") (pinfunction "E_2") (pintype "passive"))
      (node (ref "Q6") (pin "2") (pinfunction "E_2") (pintype "passive"))
      (node (ref "Q7") (pin "2") (pinfunction "E_2") (pintype "passive"))
      (node (ref "R04") (pin "2") (pinfunction "2_2") (pintype "passive"))
      (node (ref "R101") (pin "2") (pinfunction "2_2") (pintype "passive"))
      (node (ref "R14") (pin "2") (pinfunction "2_2") (pintype "passive"))
      (node (ref "R24") (pin "2") (pinfunction "2_2") (pintype "passive"))
      (node (ref "R34") (pin "2") (pinfunction "2_2") (pintype "passive"))
      (node (ref "R44") (pin "2") (pinfunction "2_2") (pintype "passive"))
      (node (ref "R54") (pin "2") (pinfunction "2_2") (pintype "passive"))
      (node (ref "R64") (pin "2") (pinfunction "2_2") (pintype "passive"))
      (node (ref "R74") (pin "2") (pinfunction "2_2") (pintype "passive"))
      (node (ref "U1") (pin "4") (pinfunction "E1#_4") (pintype "passive"))
      (node (ref "U1") (pin "5") (pinfunction "E2#_5") (pintype "passive"))
      (node (ref "U1") (pin "8") (pinfunction "GND_8") (pintype "passive"))
    )
    (net (code "36") (name "Net-(D01-A)") (class "Default")
      (node (ref "D01") (pin "1") (pinfunction "A_1") (pintype "passive"))
      (node (ref "R01") (pin "2") (pinfunction "2_2") (pintype "passive"))
    )
    (net (code "37") (name "Net-(D01-K)") (class "Default")
      (node (ref "D01") (pin "2") (pinfunction "K_2") (pintype "passive"))
      (node (ref "D02") (pin "1") (pinfunction "A_1") (pintype "passive"))
      (node (ref "K0") (pin "16") (pinfunction "16_16") (pintype "passive"))
      (node (ref "Q0") (pin "3") (pinfunction "C_3") (pintype "passive"))
    )
    (net (code "38") (name "Net-(D11-A)") (class "Default")
      (node (ref "D11") (pin "1") (pinfunction "A_1") (pintype "passive"))
      (node (ref "R11") (pin "2") (pinfunction "2_2") (pintype "passive"))
    )
    (net (code "39") (name "Net-(D11-K)") (class "Default")
      (node (ref "D11") (pin "2") (pinfunction "K_2") (pintype "passive"))
      (node (ref "D12") (pin "1") (pinfunction "A_1") (pintype "passive"))
      (node (ref "K1") (pin "16") (pinfunction "16_16") (pintype "passive"))
      (node (ref "Q1") (pin "3") (pinfunction "C_3") (pintype "passive"))
    )
    (net (code "40") (name "Net-(D21-A)") (class "Default")
      (node (ref "D21") (pin "1") (pinfunction "A_1") (pintype "passive"))
      (node (ref "R21") (pin "2") (pinfunction "2_2") (pintype "passive"))
    )
    (net (code "41") (name "Net-(D21-K)") (class "Default")
      (node (ref "D21") (pin "2") (pinfunction "K_2") (pintype "passive"))
      (node (ref "D22") (pin "1") (pinfunction "A_1") (pintype "passive"))
      (node (ref "K2") (pin "16") (pinfunction "16_16") (pintype "passive"))
      (node (ref "Q2") (pin "3") (pinfunction "C_3") (pintype "passive"))
    )
    (net (code "42") (name "Net-(D31-A)") (class "Default")
      (node (ref "D31") (pin "1") (pinfunction "A_1") (pintype "passive"))
      (node (ref "R31") (pin "2") (pinfunction "2_2") (pintype "passive"))
    )
    (net (code "43") (name "Net-(D31-K)") (class "Default")
      (node (ref "D31") (pin "2") (pinfunction "K_2") (pintype "passive"))
      (node (ref "D32") (pin "1") (pinfunction "A_1") (pintype "passive"))
      (node (ref "K3") (pin "16") (pinfunction "16_16") (pintype "passive"))
      (node (ref "Q3") (pin "3") (pinfunction "C_3") (pintype "passive"))
    )
    (net (code "44") (name "Net-(D41-A)") (class "Default")
      (node (ref "D41") (pin "1") (pinfunction "A_1") (pintype "passive"))
      (node (ref "R41") (pin "2") (pinfunction "2_2") (pintype "passive"))
    )
    (net (code "45") (name "Net-(D41-K)") (class "Default")
      (node (ref "D41") (pin "2") (pinfunction "K_2") (pintype "passive"))
      (node (ref "D42") (pin "1") (pinfunction "A_1") (pintype "passive"))
      (node (ref "K4") (pin "16") (pinfunction "16_16") (pintype "passive"))
      (node (ref "Q4") (pin "3") (pinfunction "C_3") (pintype "passive"))
    )
    (net (code "46") (name "Net-(D51-A)") (class "Default")
      (node (ref "D51") (pin "1") (pinfunction "A_1") (pintype "passive"))
      (node (ref "R51") (pin "2") (pinfunction "2_2") (pintype "passive"))
    )
    (net (code "47") (name "Net-(D51-K)") (class "Default")
      (node (ref "D51") (pin "2") (pinfunction "K_2") (pintype "passive"))
      (node (ref "D52") (pin "1") (pinfunction "A_1") (pintype "passive"))
      (node (ref "K5") (pin "16") (pinfunction "16_16") (pintype "passive"))
      (node (ref "Q5") (pin "3") (pinfunction "C_3") (pintype "passive"))
    )
    (net (code "48") (name "Net-(D61-A)") (class "Default")
      (node (ref "D61") (pin "1") (pinfunction "A_1") (pintype "passive"))
      (node (ref "R61") (pin "2") (pinfunction "2_2") (pintype "passive"))
    )
    (net (code "49") (name "Net-(D61-K)") (class "Default")
      (node (ref "D61") (pin "2") (pinfunction "K_2") (pintype "passive"))
      (node (ref "D62") (pin "1") (pinfunction "A_1") (pintype "passive"))
      (node (ref "K6") (pin "16") (pinfunction "16_16") (pintype "passive"))
      (node (ref "Q6") (pin "3") (pinfunction "C_3") (pintype "passive"))
    )
    (net (code "50") (name "Net-(D71-A)") (class "Default")
      (node (ref "D71") (pin "1") (pinfunction "A_1") (pintype "passive"))
      (node (ref "R71") (pin "2") (pinfunction "2_2") (pintype "passive"))
    )
    (net (code "51") (name "Net-(D71-K)") (class "Default")
      (node (ref "D71") (pin "2") (pinfunction "K_2") (pintype "passive"))
      (node (ref "D72") (pin "1") (pinfunction "A_1") (pintype "passive"))
      (node (ref "K7") (pin "16") (pinfunction "16_16") (pintype "passive"))
      (node (ref "Q7") (pin "3") (pinfunction "C_3") (pintype "passive"))
    )
    (net (code "52") (name "Net-(Q0-B)") (class "Default")
      (node (ref "Q0") (pin "1") (pinfunction "B_1") (pintype "passive"))
      (node (ref "R03") (pin "1") (pinfunction "1_1") (pintype "passive"))
    )
    (net (code "53") (name "Net-(Q1-B)") (class "Default")
      (node (ref "Q1") (pin "1") (pinfunction "B_1") (pintype "passive"))
      (node (ref "R13") (pin "1") (pinfunction "1_1") (pintype "passive"))
    )
    (net (code "54") (name "Net-(Q2-B)") (class "Default")
      (node (ref "Q2") (pin "1") (pinfunction "B_1") (pintype "passive"))
      (node (ref "R23") (pin "1") (pinfunction "1_1") (pintype "passive"))
    )
    (net (code "55") (name "Net-(Q3-B)") (class "Default")
      (node (ref "Q3") (pin "1") (pinfunction "B_1") (pintype "passive"))
      (node (ref "R33") (pin "1") (pinfunction "1_1") (pintype "passive"))
    )
    (net (code "56") (name "Net-(Q4-B)") (class "Default")
      (node (ref "Q4") (pin "1") (pinfunction "B_1") (pintype "passive"))
      (node (ref "R43") (pin "1") (pinfunction "1_1") (pintype "passive"))
    )
    (net (code "57") (name "Net-(Q5-B)") (class "Default")
      (node (ref "Q5") (pin "1") (pinfunction "B_1") (pintype "passive"))
      (node (ref "R53") (pin "1") (pinfunction "1_1") (pintype "passive"))
    )
    (net (code "58") (name "Net-(Q6-B)") (class "Default")
      (node (ref "Q6") (pin "1") (pinfunction "B_1") (pintype "passive"))
      (node (ref "R63") (pin "1") (pinfunction "1_1") (pintype "passive"))
    )
    (net (code "59") (name "Net-(Q7-B)") (class "Default")
      (node (ref "Q7") (pin "1") (pinfunction "B_1") (pintype "passive"))
      (node (ref "R73") (pin "1") (pinfunction "1_1") (pintype "passive"))
    )
    (net (code "60") (name "unconnected-(F1-Pad0)") (class "Default")
      (node (ref "F1") (pin "0") (pinfunction "0_0") (pintype "passive+no_connect"))
    )
    (net (code "61") (name "unconnected-(F2-Pad0)") (class "Default")
      (node (ref "F2") (pin "0") (pinfunction "0_0") (pintype "passive+no_connect"))
    )
    (net (code "62") (name "unconnected-(F3-Pad0)") (class "Default")
      (node (ref "F3") (pin "0") (pinfunction "0_0") (pintype "passive+no_connect"))
    )
    (net (code "63") (name "unconnected-(F4-Pad0)") (class "Default")
      (node (ref "F4") (pin "0") (pinfunction "0_0") (pintype "passive+no_connect"))
    )
    (net (code "64") (name "unconnected-(H002-Pad5)") (class "Default")
      (node (ref "H002") (pin "5") (pinfunction "5_5") (pintype "passive+no_connect"))
    )
    (net (code "65") (name "unconnected-(K0-Pad4)") (class "Default")
      (node (ref "K0") (pin "4") (pinfunction "4_4") (pintype "passive+no_connect"))
    )
    (net (code "66") (name "unconnected-(K0-Pad13)") (class "Default")
      (node (ref "K0") (pin "13") (pinfunction "13_13") (pintype "passive+no_connect"))
    )
    (net (code "67") (name "unconnected-(K1-Pad4)") (class "Default")
      (node (ref "K1") (pin "4") (pinfunction "4_4") (pintype "passive+no_connect"))
    )
    (net (code "68") (name "unconnected-(K1-Pad13)") (class "Default")
      (node (ref "K1") (pin "13") (pinfunction "13_13") (pintype "passive+no_connect"))
    )
    (net (code "69") (name "unconnected-(K2-Pad4)") (class "Default")
      (node (ref "K2") (pin "4") (pinfunction "4_4") (pintype "passive+no_connect"))
    )
    (net (code "70") (name "unconnected-(K2-Pad13)") (class "Default")
      (node (ref "K2") (pin "13") (pinfunction "13_13") (pintype "passive+no_connect"))
    )
    (net (code "71") (name "unconnected-(K3-Pad4)") (class "Default")
      (node (ref "K3") (pin "4") (pinfunction "4_4") (pintype "passive+no_connect"))
    )
    (net (code "72") (name "unconnected-(K3-Pad13)") (class "Default")
      (node (ref "K3") (pin "13") (pinfunction "13_13") (pintype "passive+no_connect"))
    )
    (net (code "73") (name "unconnected-(K4-Pad4)") (class "Default")
      (node (ref "K4") (pin "4") (pinfunction "4_4") (pintype "passive+no_connect"))
    )
    (net (code "74") (name "unconnected-(K4-Pad13)") (class "Default")
      (node (ref "K4") (pin "13") (pinfunction "13_13") (pintype "passive+no_connect"))
    )
    (net (code "75") (name "unconnected-(K5-Pad4)") (class "Default")
      (node (ref "K5") (pin "4") (pinfunction "4_4") (pintype "passive+no_connect"))
    )
    (net (code "76") (name "unconnected-(K5-Pad13)") (class "Default")
      (node (ref "K5") (pin "13") (pinfunction "13_13") (pintype "passive+no_connect"))
    )
    (net (code "77") (name "unconnected-(K6-Pad4)") (class "Default")
      (node (ref "K6") (pin "4") (pinfunction "4_4") (pintype "passive+no_connect"))
    )
    (net (code "78") (name "unconnected-(K6-Pad13)") (class "Default")
      (node (ref "K6") (pin "13") (pinfunction "13_13") (pintype "passive+no_connect"))
    )
    (net (code "79") (name "unconnected-(K7-Pad4)") (class "Default")
      (node (ref "K7") (pin "4") (pinfunction "4_4") (pintype "passive+no_connect"))
    )
    (net (code "80") (name "unconnected-(K7-Pad13)") (class "Default")
      (node (ref "K7") (pin "13") (pinfunction "13_13") (pintype "passive+no_connect"))
    )
  )
)
